# Controllers.net
KiCad netlist of a schematic drawn in Altium Designer
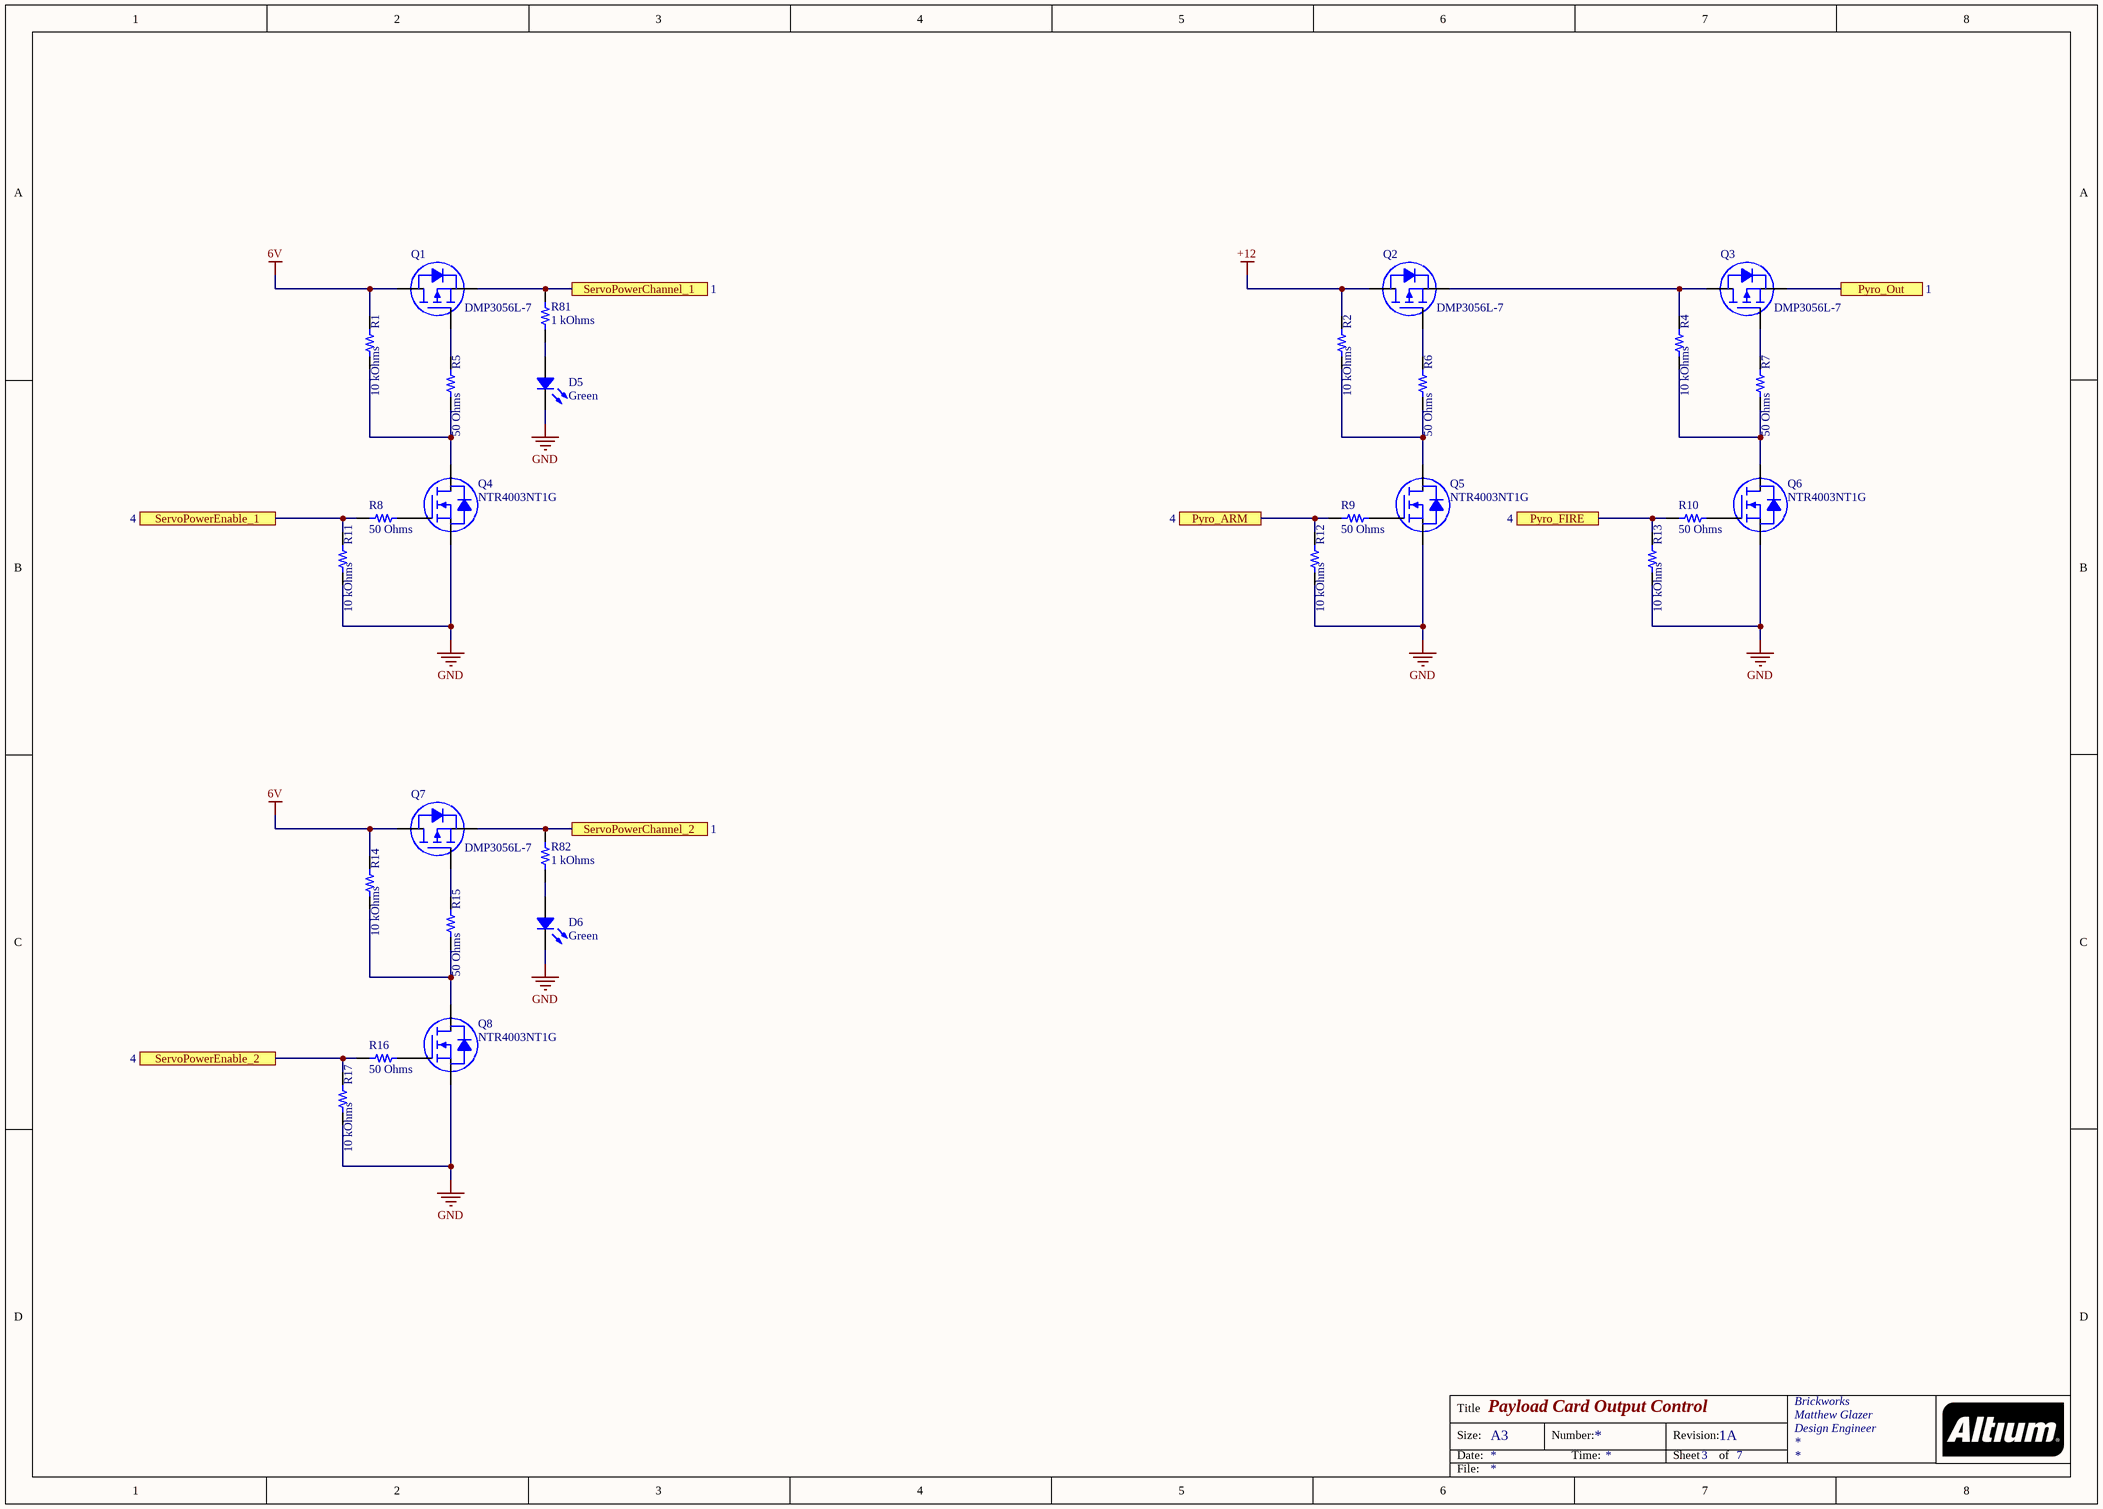
[diagram p0: Controllers.SchDoc]

(export (version "E")
  (design (tool "Eeschema 10.0.6"))
  (components
    (comp (ref "D5")
      (value "Green")
      (footprint "LED 0603_1608 GREEN")
      (description "LED GREEN CLEAR CHIP SMD")
      (fields (field (name "PART NUMBER") "LTST-C193KGKT-5A") (field (name "MANUFACTURER") "Lite-On Inc."))
      (libsource (lib "Celestial Altium Library - altium_library") (part "LED"))
    )
    (comp (ref "D6")
      (value "Green")
      (footprint "LED 0603_1608 GREEN")
      (description "LED GREEN CLEAR CHIP SMD")
      (fields (field (name "PART NUMBER") "LTST-C193KGKT-5A") (field (name "MANUFACTURER") "Lite-On Inc."))
      (libsource (lib "Celestial Altium Library - altium_library") (part "LED"))
    )
    (comp (ref "Q1")
      (value "DMP3056L-7")
      (footprint "DIODES SOT-23-3")
      (description "MOSFET P-CH 30V 4.3A SOT23")
      (fields (field (name "MANUFACTURER") "Diodes Incorporated"))
      (libsource (lib "Celestial Altium Library - altium_library") (part "DIODES MOSFET P-CH SOT-23-3"))
    )
    (comp (ref "Q2")
      (value "DMP3056L-7")
      (footprint "DIODES SOT-23-3")
      (description "MOSFET P-CH 30V 4.3A SOT23")
      (fields (field (name "MANUFACTURER") "Diodes Incorporated"))
      (libsource (lib "Celestial Altium Library - altium_library") (part "DIODES MOSFET P-CH SOT-23-3"))
    )
    (comp (ref "Q3")
      (value "DMP3056L-7")
      (footprint "DIODES SOT-23-3")
      (description "MOSFET P-CH 30V 4.3A SOT23")
      (fields (field (name "MANUFACTURER") "Diodes Incorporated"))
      (libsource (lib "Celestial Altium Library - altium_library") (part "DIODES MOSFET P-CH SOT-23-3"))
    )
    (comp (ref "Q4")
      (value "NTR4003NT1G")
      (footprint "ON SEMI SOT-23-3")
      (description "MOSFET N-CH 30V 500MA SOT-23")
      (fields (field (name "MANUFACTURER") "ON Semiconductor"))
      (libsource (lib "Celestial Altium Library - altium_library") (part "ON SEMI MOSFET N-CH SOT-23-3"))
    )
    (comp (ref "Q5")
      (value "NTR4003NT1G")
      (footprint "ON SEMI SOT-23-3")
      (description "MOSFET N-CH 30V 500MA SOT-23")
      (fields (field (name "MANUFACTURER") "ON Semiconductor"))
      (libsource (lib "Celestial Altium Library - altium_library") (part "ON SEMI MOSFET N-CH SOT-23-3"))
    )
    (comp (ref "Q6")
      (value "NTR4003NT1G")
      (footprint "ON SEMI SOT-23-3")
      (description "MOSFET N-CH 30V 500MA SOT-23")
      (fields (field (name "MANUFACTURER") "ON Semiconductor"))
      (libsource (lib "Celestial Altium Library - altium_library") (part "ON SEMI MOSFET N-CH SOT-23-3"))
    )
    (comp (ref "Q7")
      (value "DMP3056L-7")
      (footprint "DIODES SOT-23-3")
      (description "MOSFET P-CH 30V 4.3A SOT23")
      (fields (field (name "MANUFACTURER") "Diodes Incorporated"))
      (libsource (lib "Celestial Altium Library - altium_library") (part "DIODES MOSFET P-CH SOT-23-3"))
    )
    (comp (ref "Q8")
      (value "NTR4003NT1G")
      (footprint "ON SEMI SOT-23-3")
      (description "MOSFET N-CH 30V 500MA SOT-23")
      (fields (field (name "MANUFACTURER") "ON Semiconductor"))
      (libsource (lib "Celestial Altium Library - altium_library") (part "ON SEMI MOSFET N-CH SOT-23-3"))
    )
    (comp (ref "R1")
      (value "10 kOhms")
      (footprint "RES 0603_1608")
      (description "RES 10K OHM 5% 1/10W 0603")
      (fields
        (field (name "PART NUMBER") "RMCF0603JT10K0")
        (field (name "MANUFACTURER") "Stackpole Electronics Inc")
      )
      (libsource (lib "Celestial Altium Library - altium_library") (part "Resistor"))
    )
    (comp (ref "R2")
      (value "10 kOhms")
      (footprint "RES 0603_1608")
      (description "RES 10K OHM 5% 1/10W 0603")
      (fields
        (field (name "PART NUMBER") "RMCF0603JT10K0")
        (field (name "MANUFACTURER") "Stackpole Electronics Inc")
      )
      (libsource (lib "Celestial Altium Library - altium_library") (part "Resistor"))
    )
    (comp (ref "R4")
      (value "10 kOhms")
      (footprint "RES 0603_1608")
      (description "RES 10K OHM 5% 1/10W 0603")
      (fields
        (field (name "PART NUMBER") "RMCF0603JT10K0")
        (field (name "MANUFACTURER") "Stackpole Electronics Inc")
      )
      (libsource (lib "Celestial Altium Library - altium_library") (part "Resistor"))
    )
    (comp (ref "R5")
      (value "50 Ohms")
      (footprint "RES 0603_1608")
      (description "RES SMD 50 OHM 1% 1/10W 0603")
      (fields (field (name "PART NUMBER") "CRCW060350R0FKEA") (field (name "MANUFACTURER") "Vishay Dale"))
      (libsource (lib "Celestial Altium Library - altium_library") (part "Resistor"))
    )
    (comp (ref "R6")
      (value "50 Ohms")
      (footprint "RES 0603_1608")
      (description "RES SMD 50 OHM 1% 1/10W 0603")
      (fields (field (name "PART NUMBER") "CRCW060350R0FKEA") (field (name "MANUFACTURER") "Vishay Dale"))
      (libsource (lib "Celestial Altium Library - altium_library") (part "Resistor"))
    )
    (comp (ref "R7")
      (value "50 Ohms")
      (footprint "RES 0603_1608")
      (description "RES SMD 50 OHM 1% 1/10W 0603")
      (fields (field (name "PART NUMBER") "CRCW060350R0FKEA") (field (name "MANUFACTURER") "Vishay Dale"))
      (libsource (lib "Celestial Altium Library - altium_library") (part "Resistor"))
    )
    (comp (ref "R8")
      (value "50 Ohms")
      (footprint "RES 0603_1608")
      (description "RES SMD 50 OHM 1% 1/10W 0603")
      (fields (field (name "PART NUMBER") "CRCW060350R0FKEA") (field (name "MANUFACTURER") "Vishay Dale"))
      (libsource (lib "Celestial Altium Library - altium_library") (part "Resistor"))
    )
    (comp (ref "R9")
      (value "50 Ohms")
      (footprint "RES 0603_1608")
      (description "RES SMD 50 OHM 1% 1/10W 0603")
      (fields (field (name "PART NUMBER") "CRCW060350R0FKEA") (field (name "MANUFACTURER") "Vishay Dale"))
      (libsource (lib "Celestial Altium Library - altium_library") (part "Resistor"))
    )
    (comp (ref "R10")
      (value "50 Ohms")
      (footprint "RES 0603_1608")
      (description "RES SMD 50 OHM 1% 1/10W 0603")
      (fields (field (name "PART NUMBER") "CRCW060350R0FKEA") (field (name "MANUFACTURER") "Vishay Dale"))
      (libsource (lib "Celestial Altium Library - altium_library") (part "Resistor"))
    )
    (comp (ref "R11")
      (value "10 kOhms")
      (footprint "RES 0603_1608")
      (description "RES 10K OHM 5% 1/10W 0603")
      (fields
        (field (name "PART NUMBER") "RMCF0603JT10K0")
        (field (name "MANUFACTURER") "Stackpole Electronics Inc")
      )
      (libsource (lib "Celestial Altium Library - altium_library") (part "Resistor"))
    )
    (comp (ref "R12")
      (value "10 kOhms")
      (footprint "RES 0603_1608")
      (description "RES 10K OHM 5% 1/10W 0603")
      (fields
        (field (name "PART NUMBER") "RMCF0603JT10K0")
        (field (name "MANUFACTURER") "Stackpole Electronics Inc")
      )
      (libsource (lib "Celestial Altium Library - altium_library") (part "Resistor"))
    )
    (comp (ref "R13")
      (value "10 kOhms")
      (footprint "RES 0603_1608")
      (description "RES 10K OHM 5% 1/10W 0603")
      (fields
        (field (name "PART NUMBER") "RMCF0603JT10K0")
        (field (name "MANUFACTURER") "Stackpole Electronics Inc")
      )
      (libsource (lib "Celestial Altium Library - altium_library") (part "Resistor"))
    )
    (comp (ref "R14")
      (value "10 kOhms")
      (footprint "RES 0603_1608")
      (description "RES 10K OHM 5% 1/10W 0603")
      (fields
        (field (name "PART NUMBER") "RMCF0603JT10K0")
        (field (name "MANUFACTURER") "Stackpole Electronics Inc")
      )
      (libsource (lib "Celestial Altium Library - altium_library") (part "Resistor"))
    )
    (comp (ref "R15")
      (value "50 Ohms")
      (footprint "RES 0603_1608")
      (description "RES SMD 50 OHM 1% 1/10W 0603")
      (fields (field (name "PART NUMBER") "CRCW060350R0FKEA") (field (name "MANUFACTURER") "Vishay Dale"))
      (libsource (lib "Celestial Altium Library - altium_library") (part "Resistor"))
    )
    (comp (ref "R16")
      (value "50 Ohms")
      (footprint "RES 0603_1608")
      (description "RES SMD 50 OHM 1% 1/10W 0603")
      (fields (field (name "PART NUMBER") "CRCW060350R0FKEA") (field (name "MANUFACTURER") "Vishay Dale"))
      (libsource (lib "Celestial Altium Library - altium_library") (part "Resistor"))
    )
    (comp (ref "R17")
      (value "10 kOhms")
      (footprint "RES 0603_1608")
      (description "RES 10K OHM 5% 1/10W 0603")
      (fields
        (field (name "PART NUMBER") "RMCF0603JT10K0")
        (field (name "MANUFACTURER") "Stackpole Electronics Inc")
      )
      (libsource (lib "Celestial Altium Library - altium_library") (part "Resistor"))
    )
    (comp (ref "R81")
      (value "1 kOhms")
      (footprint "RES 0603_1608")
      (description "RES 1K OHM 1% 1/8W 0603")
      (fields
        (field (name "PART NUMBER") "RNCP0603FTD1K00")
        (field (name "MANUFACTURER") "Stackpole Electronics Inc")
      )
      (libsource (lib "Celestial Altium Library - altium_library") (part "Resistor"))
    )
    (comp (ref "R82")
      (value "1 kOhms")
      (footprint "RES 0603_1608")
      (description "RES 1K OHM 1% 1/8W 0603")
      (fields
        (field (name "PART NUMBER") "RNCP0603FTD1K00")
        (field (name "MANUFACTURER") "Stackpole Electronics Inc")
      )
      (libsource (lib "Celestial Altium Library - altium_library") (part "Resistor"))
    )
  )
  (nets
    (net (code "1") (name "+12") (class "Default")
      (node (ref "Q2") (pin "3") (pinfunction "D_3") (pintype "passive"))
      (node (ref "R2") (pin "2") (pinfunction "2_2") (pintype "passive"))
    )
    (net (code "2") (name "/Pyro_ARM") (class "Default")
      (node (ref "R12") (pin "2") (pinfunction "2_2") (pintype "passive"))
      (node (ref "R9") (pin "2") (pinfunction "2_2") (pintype "passive"))
    )
    (net (code "3") (name "/Pyro_FIRE") (class "Default")
      (node (ref "R10") (pin "2") (pinfunction "2_2") (pintype "passive"))
      (node (ref "R13") (pin "2") (pinfunction "2_2") (pintype "passive"))
    )
    (net (code "4") (name "/Pyro_Out") (class "Default")
      (node (ref "Q3") (pin "2") (pinfunction "S_2") (pintype "passive"))
    )
    (net (code "5") (name "/ServoPowerChannel_1") (class "Default")
      (node (ref "Q1") (pin "2") (pinfunction "S_2") (pintype "passive"))
      (node (ref "R81") (pin "2") (pinfunction "2_2") (pintype "passive"))
    )
    (net (code "6") (name "/ServoPowerChannel_2") (class "Default")
      (node (ref "Q7") (pin "2") (pinfunction "S_2") (pintype "passive"))
      (node (ref "R82") (pin "2") (pinfunction "2_2") (pintype "passive"))
    )
    (net (code "7") (name "/ServoPowerEnable_1") (class "Default")
      (node (ref "R11") (pin "2") (pinfunction "2_2") (pintype "passive"))
      (node (ref "R8") (pin "2") (pinfunction "2_2") (pintype "passive"))
    )
    (net (code "8") (name "/ServoPowerEnable_2") (class "Default")
      (node (ref "R16") (pin "2") (pinfunction "2_2") (pintype "passive"))
      (node (ref "R17") (pin "2") (pinfunction "2_2") (pintype "passive"))
    )
    (net (code "9") (name "6V") (class "Default")
      (node (ref "Q1") (pin "3") (pinfunction "D_3") (pintype "passive"))
      (node (ref "Q7") (pin "3") (pinfunction "D_3") (pintype "passive"))
      (node (ref "R1") (pin "2") (pinfunction "2_2") (pintype "passive"))
      (node (ref "R14") (pin "2") (pinfunction "2_2") (pintype "passive"))
    )
    (net (code "10") (name "GND") (class "Default")
      (node (ref "D5") (pin "2") (pinfunction "2_2") (pintype "passive"))
      (node (ref "D6") (pin "2") (pinfunction "2_2") (pintype "passive"))
      (node (ref "Q4") (pin "2") (pinfunction "S_2") (pintype "passive"))
      (node (ref "Q5") (pin "2") (pinfunction "S_2") (pintype "passive"))
      (node (ref "Q6") (pin "2") (pinfunction "S_2") (pintype "passive"))
      (node (ref "Q8") (pin "2") (pinfunction "S_2") (pintype "passive"))
      (node (ref "R11") (pin "1") (pinfunction "1_1") (pintype "passive"))
      (node (ref "R12") (pin "1") (pinfunction "1_1") (pintype "passive"))
      (node (ref "R13") (pin "1") (pinfunction "1_1") (pintype "passive"))
      (node (ref "R17") (pin "1") (pinfunction "1_1") (pintype "passive"))
    )
    (net (code "11") (name "Net-(D5-Pad1)") (class "Default")
      (node (ref "D5") (pin "1") (pinfunction "1_1") (pintype "passive"))
      (node (ref "R81") (pin "1") (pinfunction "1_1") (pintype "passive"))
    )
    (net (code "12") (name "Net-(D6-Pad1)") (class "Default")
      (node (ref "D6") (pin "1") (pinfunction "1_1") (pintype "passive"))
      (node (ref "R82") (pin "1") (pinfunction "1_1") (pintype "passive"))
    )
    (net (code "13") (name "Net-(Q1-G)") (class "Default")
      (node (ref "Q1") (pin "1") (pinfunction "G_1") (pintype "passive"))
      (node (ref "R5") (pin "2") (pinfunction "2_2") (pintype "passive"))
    )
    (net (code "14") (name "Net-(Q2-G)") (class "Default")
      (node (ref "Q2") (pin "1") (pinfunction "G_1") (pintype "passive"))
      (node (ref "R6") (pin "2") (pinfunction "2_2") (pintype "passive"))
    )
    (net (code "15") (name "Net-(Q2-S)") (class "Default")
      (node (ref "Q2") (pin "2") (pinfunction "S_2") (pintype "passive"))
      (node (ref "Q3") (pin "3") (pinfunction "D_3") (pintype "passive"))
      (node (ref "R4") (pin "2") (pinfunction "2_2") (pintype "passive"))
    )
    (net (code "16") (name "Net-(Q3-G)") (class "Default")
      (node (ref "Q3") (pin "1") (pinfunction "G_1") (pintype "passive"))
      (node (ref "R7") (pin "2") (pinfunction "2_2") (pintype "passive"))
    )
    (net (code "17") (name "Net-(Q4-D)") (class "Default")
      (node (ref "Q4") (pin "3") (pinfunction "D_3") (pintype "passive"))
      (node (ref "R1") (pin "1") (pinfunction "1_1") (pintype "passive"))
      (node (ref "R5") (pin "1") (pinfunction "1_1") (pintype "passive"))
    )
    (net (code "18") (name "Net-(Q4-G)") (class "Default")
      (node (ref "Q4") (pin "1") (pinfunction "G_1") (pintype "passive"))
      (node (ref "R8") (pin "1") (pinfunction "1_1") (pintype "passive"))
    )
    (net (code "19") (name "Net-(Q5-D)") (class "Default")
      (node (ref "Q5") (pin "3") (pinfunction "D_3") (pintype "passive"))
      (node (ref "R2") (pin "1") (pinfunction "1_1") (pintype "passive"))
      (node (ref "R6") (pin "1") (pinfunction "1_1") (pintype "passive"))
    )
    (net (code "20") (name "Net-(Q5-G)") (class "Default")
      (node (ref "Q5") (pin "1") (pinfunction "G_1") (pintype "passive"))
      (node (ref "R9") (pin "1") (pinfunction "1_1") (pintype "passive"))
    )
    (net (code "21") (name "Net-(Q6-D)") (class "Default")
      (node (ref "Q6") (pin "3") (pinfunction "D_3") (pintype "passive"))
      (node (ref "R4") (pin "1") (pinfunction "1_1") (pintype "passive"))
      (node (ref "R7") (pin "1") (pinfunction "1_1") (pintype "passive"))
    )
    (net (code "22") (name "Net-(Q6-G)") (class "Default")
      (node (ref "Q6") (pin "1") (pinfunction "G_1") (pintype "passive"))
      (node (ref "R10") (pin "1") (pinfunction "1_1") (pintype "passive"))
    )
    (net (code "23") (name "Net-(Q7-G)") (class "Default")
      (node (ref "Q7") (pin "1") (pinfunction "G_1") (pintype "passive"))
      (node (ref "R15") (pin "2") (pinfunction "2_2") (pintype "passive"))
    )
    (net (code "24") (name "Net-(Q8-D)") (class "Default")
      (node (ref "Q8") (pin "3") (pinfunction "D_3") (pintype "passive"))
      (node (ref "R14") (pin "1") (pinfunction "1_1") (pintype "passive"))
      (node (ref "R15") (pin "1") (pinfunction "1_1") (pintype "passive"))
    )
    (net (code "25") (name "Net-(Q8-G)") (class "Default")
      (node (ref "Q8") (pin "1") (pinfunction "G_1") (pintype "passive"))
      (node (ref "R16") (pin "1") (pinfunction "1_1") (pintype "passive"))
    )
  )
)
